# Sema_Driver.net
KiCad netlist of a schematic drawn in Altium Designer
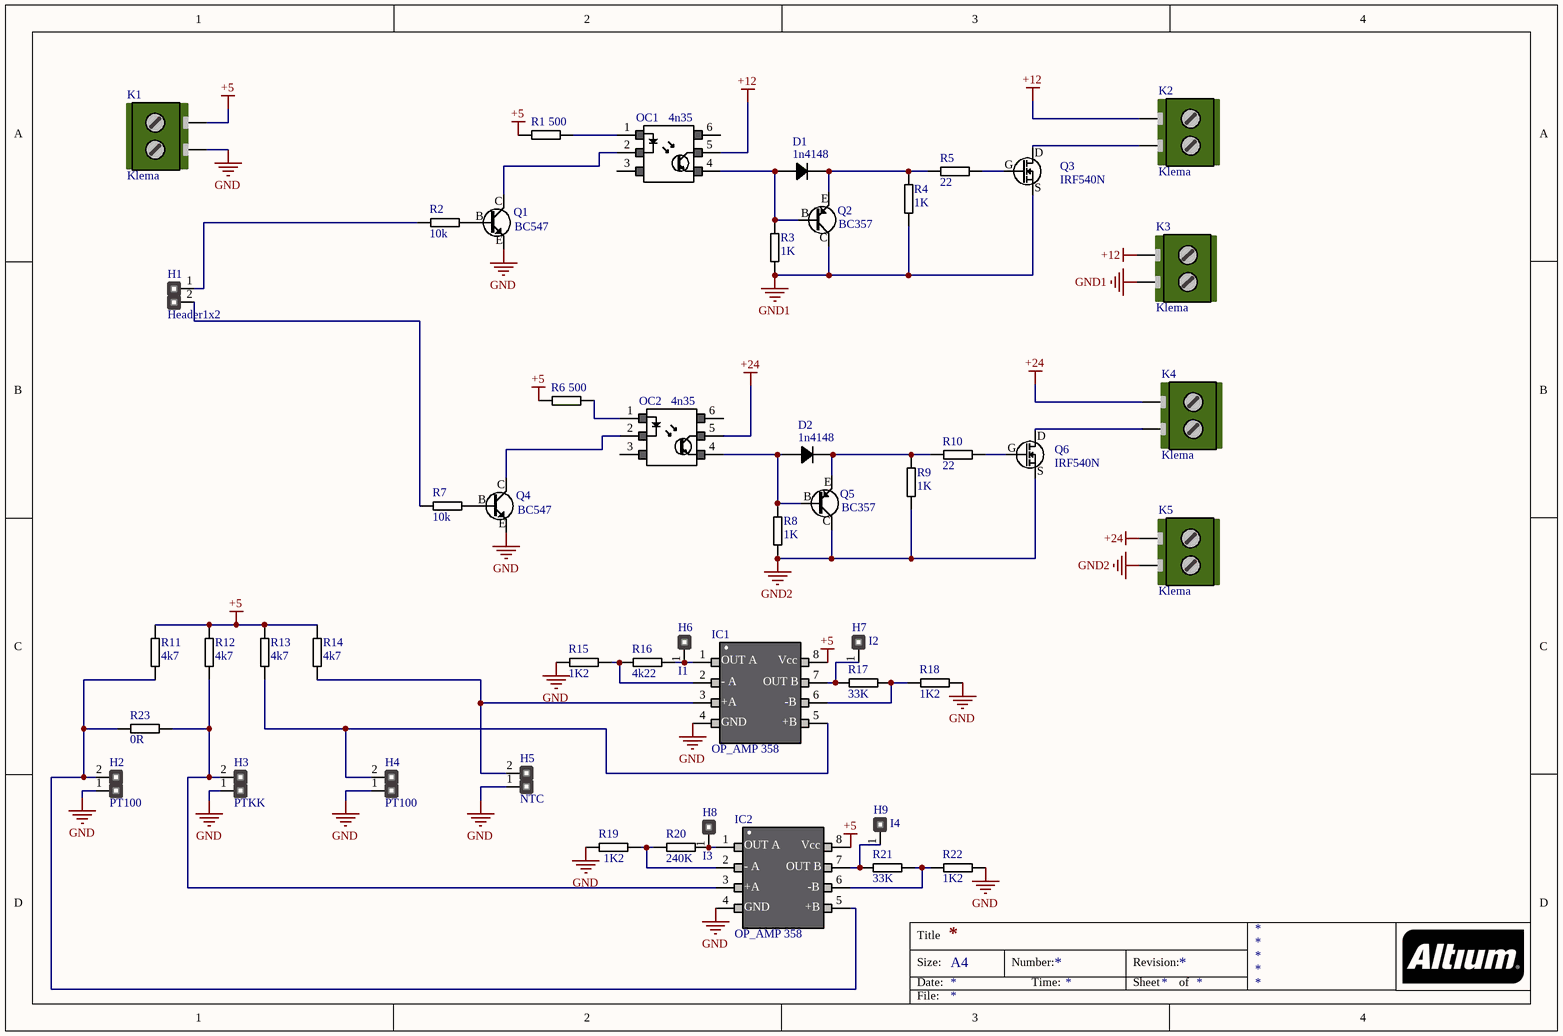
[diagram p0: Sema_Driver.SchDoc]

(export (version "E")
  (design (tool "Eeschema 10.0.6"))
  (components
    (comp (ref "D1")
      (value "1n4148")
      (footprint "D1(300milsa)")
      (libsource (lib "KILEX LIB SCH") (part "D1"))
    )
    (comp (ref "D2")
      (value "1n4148")
      (footprint "D1(300milsa)")
      (libsource (lib "KILEX LIB SCH") (part "D1"))
    )
    (comp (ref "H1") (value "Header1x2") (footprint "Header1x2") (libsource (lib "") (part "Header1x2_1")))
    (comp (ref "H2")
      (value "PT100")
      (footprint "Header1x2")
      (libsource (lib "KILEX LIB SCH") (part "Header1x2"))
    )
    (comp (ref "H3")
      (value "PTKK")
      (footprint "Header1x2")
      (libsource (lib "KILEX LIB SCH") (part "Header1x2"))
    )
    (comp (ref "H4")
      (value "PT100")
      (footprint "Header1x2")
      (libsource (lib "KILEX LIB SCH") (part "Header1x2"))
    )
    (comp (ref "H5")
      (value "NTC")
      (footprint "Header1x2")
      (libsource (lib "KILEX LIB SCH") (part "Header1x2"))
    )
    (comp (ref "H6") (value "I1") (footprint "H1x1") (libsource (lib "KILEX LIB SCH") (part "H1x1")))
    (comp (ref "H7") (value "I2") (footprint "H1x1") (libsource (lib "KILEX LIB SCH") (part "H1x1")))
    (comp (ref "H8") (value "I3") (footprint "H1x1") (libsource (lib "KILEX LIB SCH") (part "H1x1")))
    (comp (ref "H9") (value "I4") (footprint "H1x1") (libsource (lib "KILEX LIB SCH") (part "H1x1")))
    (comp (ref "IC1")
      (value "OP_AMP 358")
      (footprint "DIP8")
      (libsource (lib "KILEX LIB SCH") (part "OP_AMP 358"))
    )
    (comp (ref "IC2")
      (value "OP_AMP 358")
      (footprint "DIP8")
      (libsource (lib "KILEX LIB SCH") (part "OP_AMP 358"))
    )
    (comp (ref "K1") (value "Klema") (footprint "Klema") (libsource (lib "") (part "Klema_1")))
    (comp (ref "K2") (value "Klema") (footprint "Klema") (libsource (lib "KILEX LIB SCH") (part "Klema")))
    (comp (ref "K3") (value "Klema") (footprint "Klema") (libsource (lib "KILEX LIB SCH") (part "Klema")))
    (comp (ref "K4") (value "Klema") (footprint "Klema") (libsource (lib "KILEX LIB SCH") (part "Klema")))
    (comp (ref "K5") (value "Klema") (footprint "Klema") (libsource (lib "KILEX LIB SCH") (part "Klema")))
    (comp (ref "OC1")
      (value "4n35")
      (footprint "DIP6")
      (libsource (lib "KILEX LIB SCH") (part "4n35(optocapler)"))
    )
    (comp (ref "OC2")
      (value "4n35")
      (footprint "DIP6")
      (libsource (lib "KILEX LIB SCH") (part "4n35(optocapler)"))
    )
    (comp (ref "Q1")
      (value "BC547")
      (footprint "TO-92")
      (libsource (lib "KILEX LIB SCH") (part "Transistor NPN"))
    )
    (comp (ref "Q2")
      (value "BC357")
      (footprint "TO-92")
      (libsource (lib "KILEX LIB SCH") (part "Transistor PNP"))
    )
    (comp (ref "Q3")
      (value "IRF540N")
      (footprint "N-Channel MOSFET")
      (libsource (lib "KILEX LIB SCH") (part "N-Channel MOSFET"))
    )
    (comp (ref "Q4")
      (value "BC547")
      (footprint "TO-92")
      (libsource (lib "KILEX LIB SCH") (part "Transistor NPN"))
    )
    (comp (ref "Q5")
      (value "BC357")
      (footprint "TO-92")
      (libsource (lib "KILEX LIB SCH") (part "Transistor PNP"))
    )
    (comp (ref "Q6")
      (value "IRF540N")
      (footprint "N-Channel MOSFET")
      (libsource (lib "KILEX LIB SCH") (part "N-Channel MOSFET"))
    )
    (comp (ref "R1") (value "500") (footprint "R1(300milsa)") (libsource (lib "KILEX LIB SCH") (part "R1")))
    (comp (ref "R2") (value "10k") (footprint "R1(300milsa)") (libsource (lib "KILEX LIB SCH") (part "R1")))
    (comp (ref "R3") (value "1K") (footprint "R1(300milsa)") (libsource (lib "KILEX LIB SCH") (part "R1")))
    (comp (ref "R4") (value "1K") (footprint "R1(300milsa)") (libsource (lib "KILEX LIB SCH") (part "R1")))
    (comp (ref "R5") (value "22") (footprint "R1(300milsa)") (libsource (lib "KILEX LIB SCH") (part "R1")))
    (comp (ref "R6") (value "500") (footprint "R1(300milsa)") (libsource (lib "KILEX LIB SCH") (part "R1")))
    (comp (ref "R7") (value "10k") (footprint "R1(300milsa)") (libsource (lib "KILEX LIB SCH") (part "R1")))
    (comp (ref "R8") (value "1K") (footprint "R1(300milsa)") (libsource (lib "KILEX LIB SCH") (part "R1")))
    (comp (ref "R9") (value "1K") (footprint "R1(300milsa)") (libsource (lib "KILEX LIB SCH") (part "R1")))
    (comp (ref "R10") (value "22") (footprint "R1(300milsa)") (libsource (lib "KILEX LIB SCH") (part "R1")))
    (comp (ref "R11") (value "4k7") (footprint "R1(300milsa)") (libsource (lib "KILEX LIB SCH") (part "R1")))
    (comp (ref "R12") (value "4k7") (footprint "R1(300milsa)") (libsource (lib "KILEX LIB SCH") (part "R1")))
    (comp (ref "R13") (value "4k7") (footprint "R1(300milsa)") (libsource (lib "KILEX LIB SCH") (part "R1")))
    (comp (ref "R14") (value "4k7") (footprint "R1(300milsa)") (libsource (lib "KILEX LIB SCH") (part "R1")))
    (comp (ref "R15") (value "1K2") (footprint "R1(300milsa)") (libsource (lib "KILEX LIB SCH") (part "R1")))
    (comp (ref "R16") (value "4k22") (footprint "R1(300milsa)") (libsource (lib "KILEX LIB SCH") (part "R1")))
    (comp (ref "R17") (value "33K") (footprint "R1(300milsa)") (libsource (lib "KILEX LIB SCH") (part "R1")))
    (comp (ref "R18") (value "1K2") (footprint "R1(300milsa)") (libsource (lib "KILEX LIB SCH") (part "R1")))
    (comp (ref "R19") (value "1K2") (footprint "R1(300milsa)") (libsource (lib "KILEX LIB SCH") (part "R1")))
    (comp (ref "R20") (value "240K") (footprint "R1(300milsa)") (libsource (lib "KILEX LIB SCH") (part "R1")))
    (comp (ref "R21") (value "33K") (footprint "R1(300milsa)") (libsource (lib "KILEX LIB SCH") (part "R1")))
    (comp (ref "R22") (value "1K2") (footprint "R1(300milsa)") (libsource (lib "KILEX LIB SCH") (part "R1")))
    (comp (ref "R23") (value "0R") (footprint "R1(200milsa)") (libsource (lib "KILEX LIB SCH") (part "R1")))
  )
  (nets
    (net (code "1") (name "+5") (class "Default")
      (node (ref "IC1") (pin "8") (pinfunction "8_8") (pintype "passive"))
      (node (ref "IC2") (pin "8") (pinfunction "8_8") (pintype "passive"))
      (node (ref "K1") (pin "2") (pinfunction "2_2") (pintype "passive"))
      (node (ref "R1") (pin "2") (pinfunction "2_2") (pintype "passive"))
      (node (ref "R11") (pin "2") (pinfunction "2_2") (pintype "passive"))
      (node (ref "R12") (pin "2") (pinfunction "2_2") (pintype "passive"))
      (node (ref "R13") (pin "2") (pinfunction "2_2") (pintype "passive"))
      (node (ref "R14") (pin "1") (pinfunction "1_1") (pintype "passive"))
      (node (ref "R6") (pin "2") (pinfunction "2_2") (pintype "passive"))
    )
    (net (code "2") (name "+12") (class "Default")
      (node (ref "K2") (pin "1") (pinfunction "1_1") (pintype "passive"))
      (node (ref "K3") (pin "1") (pinfunction "1_1") (pintype "passive"))
      (node (ref "OC1") (pin "5") (pinfunction "5_5") (pintype "passive"))
    )
    (net (code "3") (name "+24") (class "Default")
      (node (ref "K4") (pin "1") (pinfunction "1_1") (pintype "passive"))
      (node (ref "K5") (pin "1") (pinfunction "1_1") (pintype "passive"))
      (node (ref "OC2") (pin "5") (pinfunction "5_5") (pintype "passive"))
    )
    (net (code "4") (name "GND") (class "Default")
      (node (ref "H2") (pin "1") (pinfunction "1_1") (pintype "passive"))
      (node (ref "H3") (pin "1") (pinfunction "1_1") (pintype "passive"))
      (node (ref "H4") (pin "1") (pinfunction "1_1") (pintype "passive"))
      (node (ref "H5") (pin "1") (pinfunction "1_1") (pintype "passive"))
      (node (ref "IC1") (pin "4") (pinfunction "4_4") (pintype "passive"))
      (node (ref "IC2") (pin "4") (pinfunction "4_4") (pintype "passive"))
      (node (ref "K1") (pin "1") (pinfunction "1_1") (pintype "passive"))
      (node (ref "Q1") (pin "2") (pinfunction "2_2") (pintype "passive"))
      (node (ref "Q4") (pin "2") (pinfunction "2_2") (pintype "passive"))
      (node (ref "R15") (pin "1") (pinfunction "1_1") (pintype "passive"))
      (node (ref "R18") (pin "2") (pinfunction "2_2") (pintype "passive"))
      (node (ref "R19") (pin "1") (pinfunction "1_1") (pintype "passive"))
      (node (ref "R22") (pin "2") (pinfunction "2_2") (pintype "passive"))
    )
    (net (code "5") (name "GND1") (class "Default")
      (node (ref "K3") (pin "2") (pinfunction "2_2") (pintype "passive"))
      (node (ref "Q2") (pin "3") (pinfunction "3_3") (pintype "passive"))
      (node (ref "Q3") (pin "3") (pinfunction "3_3") (pintype "passive"))
      (node (ref "R3") (pin "1") (pinfunction "1_1") (pintype "passive"))
      (node (ref "R4") (pin "1") (pinfunction "1_1") (pintype "passive"))
    )
    (net (code "6") (name "GND2") (class "Default")
      (node (ref "K5") (pin "2") (pinfunction "2_2") (pintype "passive"))
      (node (ref "Q5") (pin "3") (pinfunction "3_3") (pintype "passive"))
      (node (ref "Q6") (pin "3") (pinfunction "3_3") (pintype "passive"))
      (node (ref "R8") (pin "1") (pinfunction "1_1") (pintype "passive"))
      (node (ref "R9") (pin "1") (pinfunction "1_1") (pintype "passive"))
    )
    (net (code "7") (name "Net-(D1-Pad1)") (class "Default")
      (node (ref "D1") (pin "1") (pinfunction "1_1") (pintype "passive"))
      (node (ref "OC1") (pin "4") (pinfunction "4_4") (pintype "passive"))
      (node (ref "Q2") (pin "1") (pinfunction "1_1") (pintype "passive"))
      (node (ref "R3") (pin "2") (pinfunction "2_2") (pintype "passive"))
    )
    (net (code "8") (name "Net-(D1-Pad2)") (class "Default")
      (node (ref "D1") (pin "2") (pinfunction "2_2") (pintype "passive"))
      (node (ref "Q2") (pin "2") (pinfunction "2_2") (pintype "passive"))
      (node (ref "R4") (pin "2") (pinfunction "2_2") (pintype "passive"))
      (node (ref "R5") (pin "1") (pinfunction "1_1") (pintype "passive"))
    )
    (net (code "9") (name "Net-(D2-Pad1)") (class "Default")
      (node (ref "D2") (pin "1") (pinfunction "1_1") (pintype "passive"))
      (node (ref "OC2") (pin "4") (pinfunction "4_4") (pintype "passive"))
      (node (ref "Q5") (pin "1") (pinfunction "1_1") (pintype "passive"))
      (node (ref "R8") (pin "2") (pinfunction "2_2") (pintype "passive"))
    )
    (net (code "10") (name "Net-(D2-Pad2)") (class "Default")
      (node (ref "D2") (pin "2") (pinfunction "2_2") (pintype "passive"))
      (node (ref "Q5") (pin "2") (pinfunction "2_2") (pintype "passive"))
      (node (ref "R10") (pin "1") (pinfunction "1_1") (pintype "passive"))
      (node (ref "R9") (pin "2") (pinfunction "2_2") (pintype "passive"))
    )
    (net (code "11") (name "Net-(H1-Pad1)") (class "Default")
      (node (ref "H1") (pin "1") (pinfunction "1_1") (pintype "passive"))
      (node (ref "R2") (pin "1") (pinfunction "1_1") (pintype "passive"))
    )
    (net (code "12") (name "Net-(H1-Pad2)") (class "Default")
      (node (ref "H1") (pin "2") (pinfunction "2_2") (pintype "passive"))
      (node (ref "R7") (pin "1") (pinfunction "1_1") (pintype "passive"))
    )
    (net (code "13") (name "Net-(H2-Pad2)") (class "Default")
      (node (ref "H2") (pin "2") (pinfunction "2_2") (pintype "passive"))
      (node (ref "IC2") (pin "5") (pinfunction "5_5") (pintype "passive"))
      (node (ref "R11") (pin "1") (pinfunction "1_1") (pintype "passive"))
      (node (ref "R23") (pin "1") (pinfunction "1_1") (pintype "passive"))
    )
    (net (code "14") (name "Net-(H3-Pad2)") (class "Default")
      (node (ref "H3") (pin "2") (pinfunction "2_2") (pintype "passive"))
      (node (ref "IC2") (pin "3") (pinfunction "3_3") (pintype "passive"))
      (node (ref "R12") (pin "1") (pinfunction "1_1") (pintype "passive"))
      (node (ref "R23") (pin "2") (pinfunction "2_2") (pintype "passive"))
    )
    (net (code "15") (name "Net-(H4-Pad2)") (class "Default")
      (node (ref "H4") (pin "2") (pinfunction "2_2") (pintype "passive"))
      (node (ref "IC1") (pin "5") (pinfunction "5_5") (pintype "passive"))
      (node (ref "R13") (pin "1") (pinfunction "1_1") (pintype "passive"))
    )
    (net (code "16") (name "Net-(H5-Pad2)") (class "Default")
      (node (ref "H5") (pin "2") (pinfunction "2_2") (pintype "passive"))
      (node (ref "IC1") (pin "3") (pinfunction "3_3") (pintype "passive"))
      (node (ref "R14") (pin "2") (pinfunction "2_2") (pintype "passive"))
    )
    (net (code "17") (name "Net-(H6-Pad1)") (class "Default")
      (node (ref "H6") (pin "1") (pinfunction "1_1") (pintype "passive"))
      (node (ref "IC1") (pin "1") (pinfunction "1_1") (pintype "passive"))
      (node (ref "R16") (pin "2") (pinfunction "2_2") (pintype "passive"))
    )
    (net (code "18") (name "Net-(H7-Pad1)") (class "Default")
      (node (ref "H7") (pin "1") (pinfunction "1_1") (pintype "passive"))
      (node (ref "IC1") (pin "7") (pinfunction "7_7") (pintype "passive"))
      (node (ref "R17") (pin "1") (pinfunction "1_1") (pintype "passive"))
    )
    (net (code "19") (name "Net-(H8-Pad1)") (class "Default")
      (node (ref "H8") (pin "1") (pinfunction "1_1") (pintype "passive"))
      (node (ref "IC2") (pin "1") (pinfunction "1_1") (pintype "passive"))
      (node (ref "R20") (pin "2") (pinfunction "2_2") (pintype "passive"))
    )
    (net (code "20") (name "Net-(H9-Pad1)") (class "Default")
      (node (ref "H9") (pin "1") (pinfunction "1_1") (pintype "passive"))
      (node (ref "IC2") (pin "7") (pinfunction "7_7") (pintype "passive"))
      (node (ref "R21") (pin "1") (pinfunction "1_1") (pintype "passive"))
    )
    (net (code "21") (name "Net-(IC1-Pad2)") (class "Default")
      (node (ref "IC1") (pin "2") (pinfunction "2_2") (pintype "passive"))
      (node (ref "R15") (pin "2") (pinfunction "2_2") (pintype "passive"))
      (node (ref "R16") (pin "1") (pinfunction "1_1") (pintype "passive"))
    )
    (net (code "22") (name "Net-(IC1-Pad6)") (class "Default")
      (node (ref "IC1") (pin "6") (pinfunction "6_6") (pintype "passive"))
      (node (ref "R17") (pin "2") (pinfunction "2_2") (pintype "passive"))
      (node (ref "R18") (pin "1") (pinfunction "1_1") (pintype "passive"))
    )
    (net (code "23") (name "Net-(IC2-Pad2)") (class "Default")
      (node (ref "IC2") (pin "2") (pinfunction "2_2") (pintype "passive"))
      (node (ref "R19") (pin "2") (pinfunction "2_2") (pintype "passive"))
      (node (ref "R20") (pin "1") (pinfunction "1_1") (pintype "passive"))
    )
    (net (code "24") (name "Net-(IC2-Pad6)") (class "Default")
      (node (ref "IC2") (pin "6") (pinfunction "6_6") (pintype "passive"))
      (node (ref "R21") (pin "2") (pinfunction "2_2") (pintype "passive"))
      (node (ref "R22") (pin "1") (pinfunction "1_1") (pintype "passive"))
    )
    (net (code "25") (name "Net-(K2-Pad2)") (class "Default")
      (node (ref "K2") (pin "2") (pinfunction "2_2") (pintype "passive"))
      (node (ref "Q3") (pin "2") (pinfunction "2_2") (pintype "passive"))
    )
    (net (code "26") (name "Net-(K4-Pad2)") (class "Default")
      (node (ref "K4") (pin "2") (pinfunction "2_2") (pintype "passive"))
      (node (ref "Q6") (pin "2") (pinfunction "2_2") (pintype "passive"))
    )
    (net (code "27") (name "Net-(OC1-Pad1)") (class "Default")
      (node (ref "OC1") (pin "1") (pinfunction "1_1") (pintype "passive"))
      (node (ref "R1") (pin "1") (pinfunction "1_1") (pintype "passive"))
    )
    (net (code "28") (name "Net-(OC1-Pad2)") (class "Default")
      (node (ref "OC1") (pin "2") (pinfunction "2_2") (pintype "passive"))
      (node (ref "Q1") (pin "3") (pinfunction "3_3") (pintype "passive"))
    )
    (net (code "29") (name "Net-(OC2-Pad1)") (class "Default")
      (node (ref "OC2") (pin "1") (pinfunction "1_1") (pintype "passive"))
      (node (ref "R6") (pin "1") (pinfunction "1_1") (pintype "passive"))
    )
    (net (code "30") (name "Net-(OC2-Pad2)") (class "Default")
      (node (ref "OC2") (pin "2") (pinfunction "2_2") (pintype "passive"))
      (node (ref "Q4") (pin "3") (pinfunction "3_3") (pintype "passive"))
    )
    (net (code "31") (name "Net-(Q1-Pad1)") (class "Default")
      (node (ref "Q1") (pin "1") (pinfunction "1_1") (pintype "passive"))
      (node (ref "R2") (pin "2") (pinfunction "2_2") (pintype "passive"))
    )
    (net (code "32") (name "Net-(Q3-Pad1)") (class "Default")
      (node (ref "Q3") (pin "1") (pinfunction "1_1") (pintype "passive"))
      (node (ref "R5") (pin "2") (pinfunction "2_2") (pintype "passive"))
    )
    (net (code "33") (name "Net-(Q4-Pad1)") (class "Default")
      (node (ref "Q4") (pin "1") (pinfunction "1_1") (pintype "passive"))
      (node (ref "R7") (pin "2") (pinfunction "2_2") (pintype "passive"))
    )
    (net (code "34") (name "Net-(Q6-Pad1)") (class "Default")
      (node (ref "Q6") (pin "1") (pinfunction "1_1") (pintype "passive"))
      (node (ref "R10") (pin "2") (pinfunction "2_2") (pintype "passive"))
    )
    (net (code "35") (name "unconnected-(OC1-Pad3)") (class "Default")
      (node (ref "OC1") (pin "3") (pinfunction "3_3") (pintype "passive"))
    )
    (net (code "36") (name "unconnected-(OC1-Pad6)") (class "Default")
      (node (ref "OC1") (pin "6") (pinfunction "6_6") (pintype "passive"))
    )
    (net (code "37") (name "unconnected-(OC2-Pad3)") (class "Default")
      (node (ref "OC2") (pin "3") (pinfunction "3_3") (pintype "passive"))
    )
    (net (code "38") (name "unconnected-(OC2-Pad6)") (class "Default")
      (node (ref "OC2") (pin "6") (pinfunction "6_6") (pintype "passive"))
    )
  )
)
